# HIVE_BOARD_DEBUG.net
KiCad netlist of a schematic drawn in Altium Designer
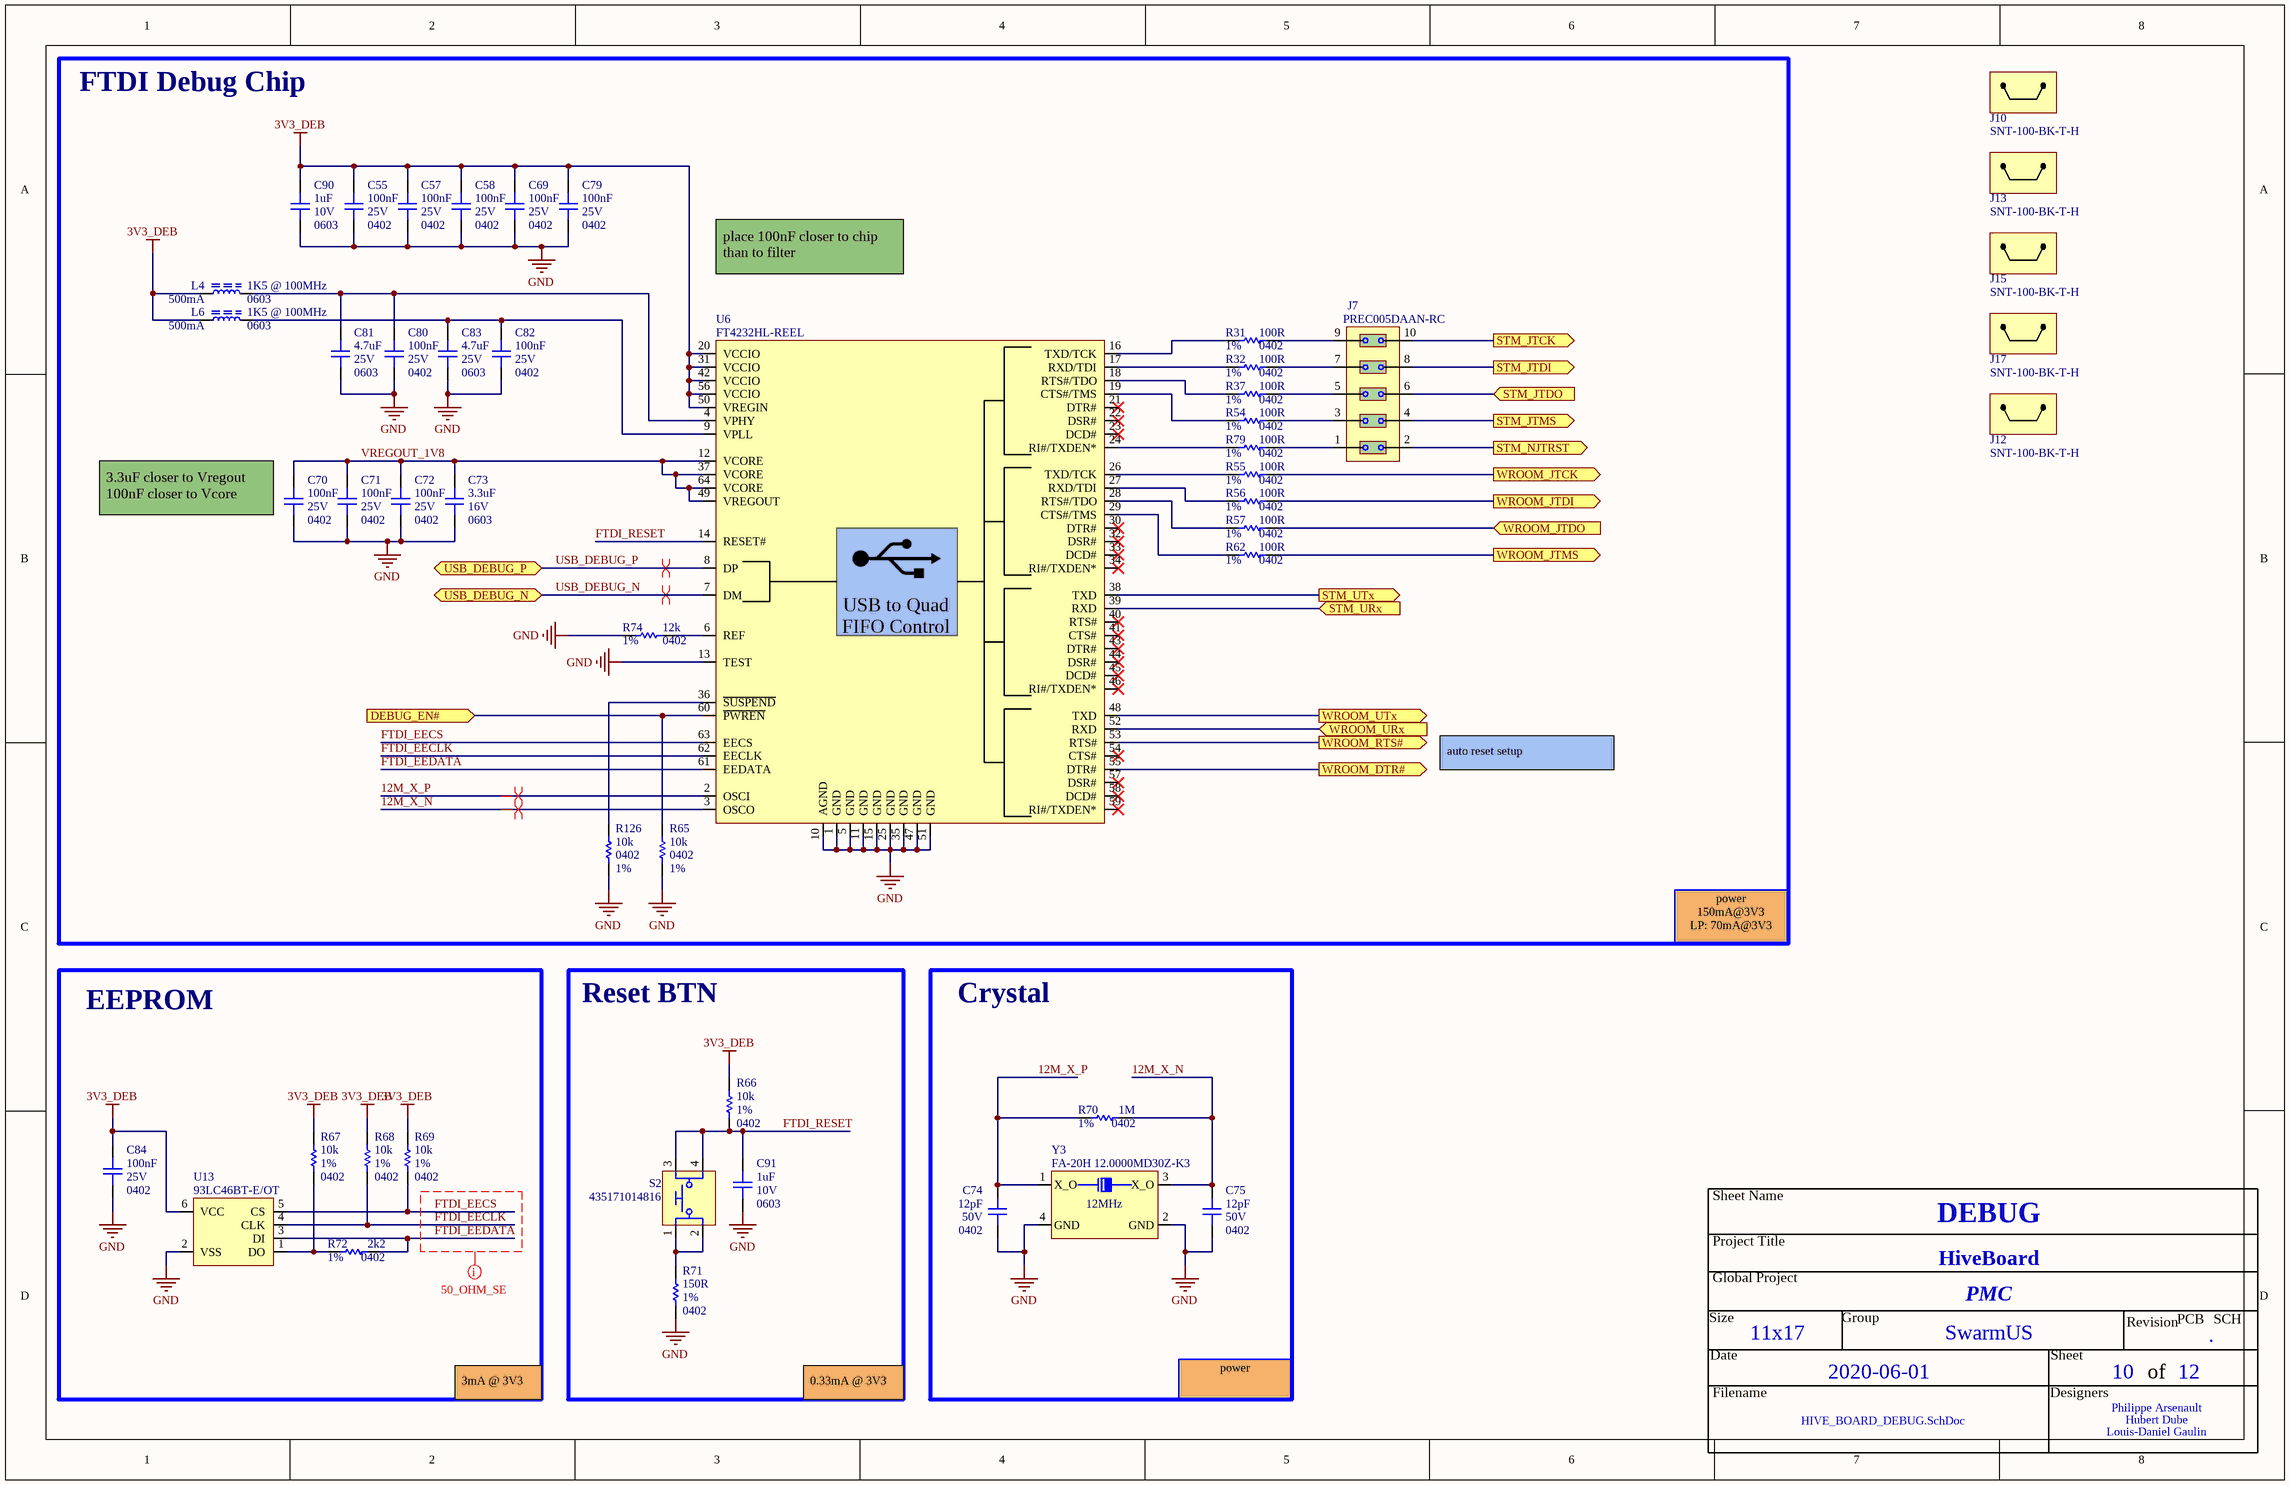
[diagram p0: HIVE_BOARD_DEBUG.SchDoc]

(export (version "E")
  (design (tool "Eeschema 10.0.6"))
  (components
    (comp (ref "C55")
      (value "100nF")
      (footprint "CAP_CER_0402")
      (description "CAP - CER 0.1µF 10% 25V X7R - 0402")
      (fields
        (field (name "TOLERANCE") "10%")
        (field (name "PACKAGE") "0402")
        (field (name "VOLTAGE RATING") "25V")
        (field (name "Comment") "CGA2B3X7R1E104K050BB")
        (field (name "CREATEDBY/DATE") "Nicolas Roy 2018-11-07")
        (field (name "VERIFIEDBY") "Nicolas V. (2019-01-22)")
      )
      (libsource (lib "GRAMS_MASTER_LIB") (part "CAP_CER_CGA2B3X7R1E104K050BB"))
    )
    (comp (ref "C57")
      (value "100nF")
      (footprint "CAP_CER_0402")
      (description "CAP - CER 0.1µF 10% 25V X7R - 0402")
      (fields
        (field (name "TOLERANCE") "10%")
        (field (name "PACKAGE") "0402")
        (field (name "VOLTAGE RATING") "25V")
        (field (name "Comment") "CGA2B3X7R1E104K050BB")
        (field (name "CREATEDBY/DATE") "Nicolas Roy 2018-11-07")
        (field (name "VERIFIEDBY") "Nicolas V. (2019-01-22)")
      )
      (libsource (lib "GRAMS_MASTER_LIB") (part "CAP_CER_CGA2B3X7R1E104K050BB"))
    )
    (comp (ref "C58")
      (value "100nF")
      (footprint "CAP_CER_0402")
      (description "CAP - CER 0.1µF 10% 25V X7R - 0402")
      (fields
        (field (name "TOLERANCE") "10%")
        (field (name "PACKAGE") "0402")
        (field (name "VOLTAGE RATING") "25V")
        (field (name "Comment") "CGA2B3X7R1E104K050BB")
        (field (name "CREATEDBY/DATE") "Nicolas Roy 2018-11-07")
        (field (name "VERIFIEDBY") "Nicolas V. (2019-01-22)")
      )
      (libsource (lib "GRAMS_MASTER_LIB") (part "CAP_CER_CGA2B3X7R1E104K050BB"))
    )
    (comp (ref "C69")
      (value "100nF")
      (footprint "CAP_CER_0402")
      (description "CAP - CER 0.1µF 10% 25V X7R - 0402")
      (fields
        (field (name "TOLERANCE") "10%")
        (field (name "PACKAGE") "0402")
        (field (name "VOLTAGE RATING") "25V")
        (field (name "Comment") "CGA2B3X7R1E104K050BB")
        (field (name "CREATEDBY/DATE") "Nicolas Roy 2018-11-07")
        (field (name "VERIFIEDBY") "Nicolas V. (2019-01-22)")
      )
      (libsource (lib "GRAMS_MASTER_LIB") (part "CAP_CER_CGA2B3X7R1E104K050BB"))
    )
    (comp (ref "C70")
      (value "100nF")
      (footprint "CAP_CER_0402")
      (description "CAP - CER 0.1µF 10% 25V X7R - 0402")
      (fields
        (field (name "TOLERANCE") "10%")
        (field (name "PACKAGE") "0402")
        (field (name "VOLTAGE RATING") "25V")
        (field (name "Comment") "CGA2B3X7R1E104K050BB")
        (field (name "CREATEDBY/DATE") "Nicolas Roy 2018-11-07")
        (field (name "VERIFIEDBY") "Nicolas V. (2019-01-22)")
      )
      (libsource (lib "GRAMS_MASTER_LIB") (part "CAP_CER_CGA2B3X7R1E104K050BB"))
    )
    (comp (ref "C71")
      (value "100nF")
      (footprint "CAP_CER_0402")
      (description "CAP - CER 0.1µF 10% 25V X7R - 0402")
      (fields
        (field (name "TOLERANCE") "10%")
        (field (name "PACKAGE") "0402")
        (field (name "VOLTAGE RATING") "25V")
        (field (name "Comment") "CGA2B3X7R1E104K050BB")
        (field (name "CREATEDBY/DATE") "Nicolas Roy 2018-11-07")
        (field (name "VERIFIEDBY") "Nicolas V. (2019-01-22)")
      )
      (libsource (lib "GRAMS_MASTER_LIB") (part "CAP_CER_CGA2B3X7R1E104K050BB"))
    )
    (comp (ref "C72")
      (value "100nF")
      (footprint "CAP_CER_0402")
      (description "CAP - CER 0.1µF 10% 25V X7R - 0402")
      (fields
        (field (name "TOLERANCE") "10%")
        (field (name "PACKAGE") "0402")
        (field (name "VOLTAGE RATING") "25V")
        (field (name "Comment") "CGA2B3X7R1E104K050BB")
        (field (name "CREATEDBY/DATE") "Nicolas Roy 2018-11-07")
        (field (name "VERIFIEDBY") "Nicolas V. (2019-01-22)")
      )
      (libsource (lib "GRAMS_MASTER_LIB") (part "CAP_CER_CGA2B3X7R1E104K050BB"))
    )
    (comp (ref "C73")
      (value "3.3uF")
      (footprint "CAP_CER_0603")
      (description "CAP - CER 3.3µF ±10% 16V Ceramic Capacitor X5R 0603 (1608 Metric)")
      (fields
        (field (name "TOLERANCE") "10%")
        (field (name "PACKAGE") "0603")
        (field (name "VOLTAGE RATING") "16V")
        (field (name "Comment") "C1608X5R1C335K080AC")
        (field (name "CREATEDBY/DATE") "Hubert Dube - 16/03/2021")
        (field (name "VERIFIEDBY") "Philippe Arsenault - 2021/03/16")
      )
      (libsource (lib "SWARMUS_LIB") (part "CAP_CER_C1608X5R1C335K080AC"))
    )
    (comp (ref "C74")
      (value "12pF")
      (footprint "CAP_CER_0402")
      (description "CAP - CER 12pF 50V ±5% C0G, NP0 - 0402")
      (fields
        (field (name "TOLERANCE") "±5%")
        (field (name "PACKAGE") "0402")
        (field (name "VOLTAGE RATING") "50V")
        (field (name "Comment") "CC0402JRNPO9BN120")
        (field (name "CREATEDBY/DATE") "Philippe Arsenault/ 2020-07-24")
        (field (name "VERIFIEDBY") "Louis-Daniel Gaulin / 2020-07-29")
      )
      (libsource (lib "SWARMUS_LIB") (part "CAP_CER_CC0402JRNPO9BN120"))
    )
    (comp (ref "C75")
      (value "12pF")
      (footprint "CAP_CER_0402")
      (description "CAP - CER 12pF 50V ±5% C0G, NP0 - 0402")
      (fields
        (field (name "TOLERANCE") "±5%")
        (field (name "PACKAGE") "0402")
        (field (name "VOLTAGE RATING") "50V")
        (field (name "Comment") "CC0402JRNPO9BN120")
        (field (name "CREATEDBY/DATE") "Philippe Arsenault/ 2020-07-24")
        (field (name "VERIFIEDBY") "Louis-Daniel Gaulin / 2020-07-29")
      )
      (libsource (lib "SWARMUS_LIB") (part "CAP_CER_CC0402JRNPO9BN120"))
    )
    (comp (ref "C79")
      (value "100nF")
      (footprint "CAP_CER_0402")
      (description "CAP - CER 0.1µF 10% 25V X7R - 0402")
      (fields
        (field (name "TOLERANCE") "10%")
        (field (name "PACKAGE") "0402")
        (field (name "VOLTAGE RATING") "25V")
        (field (name "Comment") "CGA2B3X7R1E104K050BB")
        (field (name "CREATEDBY/DATE") "Nicolas Roy 2018-11-07")
        (field (name "VERIFIEDBY") "Nicolas V. (2019-01-22)")
      )
      (libsource (lib "GRAMS_MASTER_LIB") (part "CAP_CER_CGA2B3X7R1E104K050BB"))
    )
    (comp (ref "C80")
      (value "100nF")
      (footprint "CAP_CER_0402")
      (description "CAP - CER 0.1µF 10% 25V X7R - 0402")
      (fields
        (field (name "TOLERANCE") "10%")
        (field (name "PACKAGE") "0402")
        (field (name "VOLTAGE RATING") "25V")
        (field (name "Comment") "CGA2B3X7R1E104K050BB")
        (field (name "CREATEDBY/DATE") "Nicolas Roy 2018-11-07")
        (field (name "VERIFIEDBY") "Nicolas V. (2019-01-22)")
      )
      (libsource (lib "GRAMS_MASTER_LIB") (part "CAP_CER_CGA2B3X7R1E104K050BB"))
    )
    (comp (ref "C81")
      (value "4.7uF")
      (footprint "CAP_CER_0603")
      (description "CAP - CER 4.7µF 20% 25V X5R - 0603")
      (fields
        (field (name "TOLERANCE") "20%")
        (field (name "PACKAGE") "0603")
        (field (name "VOLTAGE RATING") "25V")
        (field (name "Comment") "CL10A475MA8NQNC")
        (field (name "CREATEDBY/DATE") "Nicolas Roy 2018-11-21")
        (field (name "VERIFIEDBY") "Nicolas V. (2019-01-22)")
      )
      (libsource (lib "GRAMS_MASTER_LIB") (part "CAP_CER_CL10A475MA8NQNC"))
    )
    (comp (ref "C82")
      (value "100nF")
      (footprint "CAP_CER_0402")
      (description "CAP - CER 0.1µF 10% 25V X7R - 0402")
      (fields
        (field (name "TOLERANCE") "10%")
        (field (name "PACKAGE") "0402")
        (field (name "VOLTAGE RATING") "25V")
        (field (name "Comment") "CGA2B3X7R1E104K050BB")
        (field (name "CREATEDBY/DATE") "Nicolas Roy 2018-11-07")
        (field (name "VERIFIEDBY") "Nicolas V. (2019-01-22)")
      )
      (libsource (lib "GRAMS_MASTER_LIB") (part "CAP_CER_CGA2B3X7R1E104K050BB"))
    )
    (comp (ref "C83")
      (value "4.7uF")
      (footprint "CAP_CER_0603")
      (description "CAP - CER 4.7µF 20% 25V X5R - 0603")
      (fields
        (field (name "TOLERANCE") "20%")
        (field (name "PACKAGE") "0603")
        (field (name "VOLTAGE RATING") "25V")
        (field (name "Comment") "CL10A475MA8NQNC")
        (field (name "CREATEDBY/DATE") "Nicolas Roy 2018-11-21")
        (field (name "VERIFIEDBY") "Nicolas V. (2019-01-22)")
      )
      (libsource (lib "GRAMS_MASTER_LIB") (part "CAP_CER_CL10A475MA8NQNC"))
    )
    (comp (ref "C84")
      (value "100nF")
      (footprint "CAP_CER_0402")
      (description "CAP - CER 0.1µF 10% 25V X7R - 0402")
      (fields
        (field (name "TOLERANCE") "10%")
        (field (name "PACKAGE") "0402")
        (field (name "VOLTAGE RATING") "25V")
        (field (name "Comment") "CGA2B3X7R1E104K050BB")
        (field (name "CREATEDBY/DATE") "Nicolas Roy 2018-11-07")
        (field (name "VERIFIEDBY") "Nicolas V. (2019-01-22)")
      )
      (libsource (lib "GRAMS_MASTER_LIB") (part "CAP_CER_CGA2B3X7R1E104K050BB"))
    )
    (comp (ref "C90")
      (value "1uF")
      (footprint "CAP_CER_0603")
      (description "CAP - CER 1uF 10V 10% X5R - 0603")
      (fields
        (field (name "TOLERANCE") "10%")
        (field (name "PACKAGE") "0603")
        (field (name "VOLTAGE RATING") "10V")
        (field (name "Comment") "C0603C105K8PACTU")
        (field (name "CREATEDBY/DATE") "Hubert Dube - 21/07/20")
        (field (name "VERIFIEDBY") "Louis-Daniel Gaulin - 21/07/20")
      )
      (libsource (lib "SWARMUS_LIB") (part "CAP_CER_C0603C105K8PACTU"))
    )
    (comp (ref "C91")
      (value "1uF")
      (footprint "CAP_CER_0603")
      (description "CAP - CER 1uF 10V 10% X5R - 0603")
      (fields
        (field (name "TOLERANCE") "10%")
        (field (name "PACKAGE") "0603")
        (field (name "VOLTAGE RATING") "10V")
        (field (name "Comment") "C0603C105K8PACTU")
        (field (name "CREATEDBY/DATE") "Hubert Dube - 21/07/20")
        (field (name "VERIFIEDBY") "Louis-Daniel Gaulin - 21/07/20")
      )
      (libsource (lib "SWARMUS_LIB") (part "CAP_CER_C0603C105K8PACTU"))
    )
    (comp (ref "J7")
      (value "PREC005DAAN-RC")
      (footprint "CON_HDR_PREC009DAAN-RC")
      (description "CON - Connector Header Through Hole 10 position 0.100\" (2.54mm)")
      (fields
        (field (name "VERIFIEDBY") "Louis-Daniel Gaulin / 08-04-2021")
        (field (name "CREATEDBY/DATE") "Philippe Arsenault/2021-03-27")
      )
      (libsource (lib "SWARMUS_LIB") (part "CON_HDR_PREC005DAAN-RC"))
    )
    (comp (ref "J10")
      (value "SNT-100-BK-T-H")
      (footprint "CON_JMP_SNT-100-BK-T-H")
      (description "CON - CONN SHUNT - MEC")
      (fields
        (field (name "CREATEDBY/DATE") "Arnaud Samson - 09/07/18")
        (field (name "VERIFIEDBY") "Jonathan Bouchard 2018-07-12")
      )
      (libsource (lib "GRAMS_MASTER_LIB") (part "CON_JMP_SNT-100-BK-T-H"))
    )
    (comp (ref "J12")
      (value "SNT-100-BK-T-H")
      (footprint "CON_JMP_SNT-100-BK-T-H")
      (description "CON - CONN SHUNT - MEC")
      (fields
        (field (name "CREATEDBY/DATE") "Arnaud Samson - 09/07/18")
        (field (name "VERIFIEDBY") "Jonathan Bouchard 2018-07-12")
      )
      (libsource (lib "GRAMS_MASTER_LIB") (part "CON_JMP_SNT-100-BK-T-H"))
    )
    (comp (ref "J13")
      (value "SNT-100-BK-T-H")
      (footprint "CON_JMP_SNT-100-BK-T-H")
      (description "CON - CONN SHUNT - MEC")
      (fields
        (field (name "CREATEDBY/DATE") "Arnaud Samson - 09/07/18")
        (field (name "VERIFIEDBY") "Jonathan Bouchard 2018-07-12")
      )
      (libsource (lib "GRAMS_MASTER_LIB") (part "CON_JMP_SNT-100-BK-T-H"))
    )
    (comp (ref "J15")
      (value "SNT-100-BK-T-H")
      (footprint "CON_JMP_SNT-100-BK-T-H")
      (description "CON - CONN SHUNT - MEC")
      (fields
        (field (name "CREATEDBY/DATE") "Arnaud Samson - 09/07/18")
        (field (name "VERIFIEDBY") "Jonathan Bouchard 2018-07-12")
      )
      (libsource (lib "GRAMS_MASTER_LIB") (part "CON_JMP_SNT-100-BK-T-H"))
    )
    (comp (ref "J17")
      (value "SNT-100-BK-T-H")
      (footprint "CON_JMP_SNT-100-BK-T-H")
      (description "CON - CONN SHUNT - MEC")
      (fields
        (field (name "CREATEDBY/DATE") "Arnaud Samson - 09/07/18")
        (field (name "VERIFIEDBY") "Jonathan Bouchard 2018-07-12")
      )
      (libsource (lib "GRAMS_MASTER_LIB") (part "CON_JMP_SNT-100-BK-T-H"))
    )
    (comp (ref "L4")
      (value "1K5 @ 100MHz")
      (footprint "FER_0603")
      (description "FER - 1.5 kOhms @ 100MHz 1 Signal Line Ferrite Bead 0603 (1608 Metric) 500mA 500mOhm DC")
      (fields
        (field (name "CURRENT RATING") "500mA")
        (field (name "PACKAGE") "0603")
        (field (name "Comment") "BLM18HE152SN1D")
        (field (name "CREATEDBY/DATE") "Hubert Dube - 16/03/2021")
        (field (name "VERIFIEDBY") "Philippe Arsenault - 2021-03-16")
      )
      (libsource (lib "SWARMUS_LIB") (part "FER_BLM18HE152SN1D"))
    )
    (comp (ref "L6")
      (value "1K5 @ 100MHz")
      (footprint "FER_0603")
      (description "FER - 1.5 kOhms @ 100MHz 1 Signal Line Ferrite Bead 0603 (1608 Metric) 500mA 500mOhm DC")
      (fields
        (field (name "CURRENT RATING") "500mA")
        (field (name "PACKAGE") "0603")
        (field (name "Comment") "BLM18HE152SN1D")
        (field (name "CREATEDBY/DATE") "Hubert Dube - 16/03/2021")
        (field (name "VERIFIEDBY") "Philippe Arsenault - 2021-03-16")
      )
      (libsource (lib "SWARMUS_LIB") (part "FER_BLM18HE152SN1D"))
    )
    (comp (ref "R31")
      (value "100R")
      (footprint "RES_0402")
      (description "RES - 100R OHM 1% 1/16W - 0402")
      (fields
        (field (name "TOLERANCE") "1%")
        (field (name "PACKAGE") "0402")
        (field (name "Comment") "RC0402FR-07100RP")
        (field (name "CREATEDBY/DATE") "Jonathan Bouchard 2018-07-05")
        (field (name "VERIFIEDBY") "Arnaud Samson 16-07-18")
      )
      (libsource (lib "GRAMS_MASTER_LIB") (part "RES_RC0402FR-07100RP"))
    )
    (comp (ref "R32")
      (value "100R")
      (footprint "RES_0402")
      (description "RES - 100R OHM 1% 1/16W - 0402")
      (fields
        (field (name "TOLERANCE") "1%")
        (field (name "PACKAGE") "0402")
        (field (name "Comment") "RC0402FR-07100RP")
        (field (name "CREATEDBY/DATE") "Jonathan Bouchard 2018-07-05")
        (field (name "VERIFIEDBY") "Arnaud Samson 16-07-18")
      )
      (libsource (lib "GRAMS_MASTER_LIB") (part "RES_RC0402FR-07100RP"))
    )
    (comp (ref "R37")
      (value "100R")
      (footprint "RES_0402")
      (description "RES - 100R OHM 1% 1/16W - 0402")
      (fields
        (field (name "TOLERANCE") "1%")
        (field (name "PACKAGE") "0402")
        (field (name "Comment") "RC0402FR-07100RP")
        (field (name "CREATEDBY/DATE") "Jonathan Bouchard 2018-07-05")
        (field (name "VERIFIEDBY") "Arnaud Samson 16-07-18")
      )
      (libsource (lib "GRAMS_MASTER_LIB") (part "RES_RC0402FR-07100RP"))
    )
    (comp (ref "R54")
      (value "100R")
      (footprint "RES_0402")
      (description "RES - 100R OHM 1% 1/16W - 0402")
      (fields
        (field (name "TOLERANCE") "1%")
        (field (name "PACKAGE") "0402")
        (field (name "Comment") "RC0402FR-07100RP")
        (field (name "CREATEDBY/DATE") "Jonathan Bouchard 2018-07-05")
        (field (name "VERIFIEDBY") "Arnaud Samson 16-07-18")
      )
      (libsource (lib "GRAMS_MASTER_LIB") (part "RES_RC0402FR-07100RP"))
    )
    (comp (ref "R55")
      (value "100R")
      (footprint "RES_0402")
      (description "RES - 100R OHM 1% 1/16W - 0402")
      (fields
        (field (name "TOLERANCE") "1%")
        (field (name "PACKAGE") "0402")
        (field (name "Comment") "RC0402FR-07100RP")
        (field (name "CREATEDBY/DATE") "Jonathan Bouchard 2018-07-05")
        (field (name "VERIFIEDBY") "Arnaud Samson 16-07-18")
      )
      (libsource (lib "GRAMS_MASTER_LIB") (part "RES_RC0402FR-07100RP"))
    )
    (comp (ref "R56")
      (value "100R")
      (footprint "RES_0402")
      (description "RES - 100R OHM 1% 1/16W - 0402")
      (fields
        (field (name "TOLERANCE") "1%")
        (field (name "PACKAGE") "0402")
        (field (name "Comment") "RC0402FR-07100RP")
        (field (name "CREATEDBY/DATE") "Jonathan Bouchard 2018-07-05")
        (field (name "VERIFIEDBY") "Arnaud Samson 16-07-18")
      )
      (libsource (lib "GRAMS_MASTER_LIB") (part "RES_RC0402FR-07100RP"))
    )
    (comp (ref "R57")
      (value "100R")
      (footprint "RES_0402")
      (description "RES - 100R OHM 1% 1/16W - 0402")
      (fields
        (field (name "TOLERANCE") "1%")
        (field (name "PACKAGE") "0402")
        (field (name "Comment") "RC0402FR-07100RP")
        (field (name "CREATEDBY/DATE") "Jonathan Bouchard 2018-07-05")
        (field (name "VERIFIEDBY") "Arnaud Samson 16-07-18")
      )
      (libsource (lib "GRAMS_MASTER_LIB") (part "RES_RC0402FR-07100RP"))
    )
    (comp (ref "R62")
      (value "100R")
      (footprint "RES_0402")
      (description "RES - 100R OHM 1% 1/16W - 0402")
      (fields
        (field (name "TOLERANCE") "1%")
        (field (name "PACKAGE") "0402")
        (field (name "Comment") "RC0402FR-07100RP")
        (field (name "CREATEDBY/DATE") "Jonathan Bouchard 2018-07-05")
        (field (name "VERIFIEDBY") "Arnaud Samson 16-07-18")
      )
      (libsource (lib "GRAMS_MASTER_LIB") (part "RES_RC0402FR-07100RP"))
    )
    (comp (ref "R65")
      (value "10k")
      (footprint "RES_0402")
      (description "RES - 10K OHMS 1% 1/16W - 0402")
      (fields
        (field (name "TOLERANCE") "1%")
        (field (name "PACKAGE") "0402")
        (field (name "Comment") "RC0402FR-0710KL")
        (field (name "CREATEDBY/DATE") "Nicolas V. (2018-11-20)")
        (field (name "VERIFIEDBY") "Nicolas V. (2018-11-20)")
      )
      (libsource (lib "GRAMS_MASTER_LIB") (part "RES_RC0402FR-0710KL"))
    )
    (comp (ref "R66")
      (value "10k")
      (footprint "RES_0402")
      (description "RES - 10K OHMS 1% 1/16W - 0402")
      (fields
        (field (name "TOLERANCE") "1%")
        (field (name "PACKAGE") "0402")
        (field (name "Comment") "RC0402FR-0710KL")
        (field (name "CREATEDBY/DATE") "Nicolas V. (2018-11-20)")
        (field (name "VERIFIEDBY") "Nicolas V. (2018-11-20)")
      )
      (libsource (lib "GRAMS_MASTER_LIB") (part "RES_RC0402FR-0710KL"))
    )
    (comp (ref "R67")
      (value "10k")
      (footprint "RES_0402")
      (description "RES - 10K OHMS 1% 1/16W - 0402")
      (fields
        (field (name "TOLERANCE") "1%")
        (field (name "PACKAGE") "0402")
        (field (name "Comment") "RC0402FR-0710KL")
        (field (name "CREATEDBY/DATE") "Nicolas V. (2018-11-20)")
        (field (name "VERIFIEDBY") "Nicolas V. (2018-11-20)")
      )
      (libsource (lib "GRAMS_MASTER_LIB") (part "RES_RC0402FR-0710KL"))
    )
    (comp (ref "R68")
      (value "10k")
      (footprint "RES_0402")
      (description "RES - 10K OHMS 1% 1/16W - 0402")
      (fields
        (field (name "TOLERANCE") "1%")
        (field (name "PACKAGE") "0402")
        (field (name "Comment") "RC0402FR-0710KL")
        (field (name "CREATEDBY/DATE") "Nicolas V. (2018-11-20)")
        (field (name "VERIFIEDBY") "Nicolas V. (2018-11-20)")
      )
      (libsource (lib "GRAMS_MASTER_LIB") (part "RES_RC0402FR-0710KL"))
    )
    (comp (ref "R69")
      (value "10k")
      (footprint "RES_0402")
      (description "RES - 10K OHMS 1% 1/16W - 0402")
      (fields
        (field (name "TOLERANCE") "1%")
        (field (name "PACKAGE") "0402")
        (field (name "Comment") "RC0402FR-0710KL")
        (field (name "CREATEDBY/DATE") "Nicolas V. (2018-11-20)")
        (field (name "VERIFIEDBY") "Nicolas V. (2018-11-20)")
      )
      (libsource (lib "GRAMS_MASTER_LIB") (part "RES_RC0402FR-0710KL"))
    )
    (comp (ref "R70")
      (value "1M")
      (footprint "RES_0402")
      (description "RES - 1 MOhms ±1% 0.063W, 1/16W Chip Resistor 0402 (1005 Metric) Moisture Resistant Thick Film")
      (fields
        (field (name "TOLERANCE") "1%")
        (field (name "PACKAGE") "0402")
        (field (name "Comment") "RC0402FR-071ML")
        (field (name "CREATEDBY/DATE") "Hubert Dube 16/03/2021")
        (field (name "VERIFIEDBY") "Philippe Arsenault - 2021/03/16")
      )
      (libsource (lib "SWARMUS_LIB") (part "RES_RC0402FR-071ML"))
    )
    (comp (ref "R71")
      (value "150R")
      (footprint "RES_0402")
      (description "RES - 150R 1% 1/16W - 0402")
      (fields
        (field (name "TOLERANCE") "1%")
        (field (name "PACKAGE") "0402")
        (field (name "Comment") "RC0402FR-07150RL")
        (field (name "CREATEDBY/DATE") "Jonathan Bouchard 2019-03-25")
        (field (name "VERIFIEDBY") "Nicolas V. (2019-05-02)")
      )
      (libsource (lib "GRAMS_MASTER_LIB") (part "RES_RC0402FR-07150RL"))
    )
    (comp (ref "R72")
      (value "2k2")
      (footprint "RES_0402")
      (description "RES - 2.2K 1% 1/16W - 0402")
      (fields
        (field (name "TOLERANCE") "1%")
        (field (name "PACKAGE") "0402")
        (field (name "Comment") "RC0402FR-072K2L")
        (field (name "CREATEDBY/DATE") "Keven Deslandes 2018-11-14")
        (field (name "VERIFIEDBY") "Caroline Paulin - 8 janv 2019")
      )
      (libsource (lib "GRAMS_MASTER_LIB") (part "RES_RC0402FR-072K2L"))
    )
    (comp (ref "R74")
      (value "12k")
      (footprint "RES_0402")
      (description "RES - 12k Ohms ±1% 0.063W, 1/16W Chip Resistor 0402 (1005 Metric) Moisture Resistant Thick Film")
      (fields
        (field (name "TOLERANCE") "1%")
        (field (name "PACKAGE") "0402")
        (field (name "Comment") "RC0402FR-0712KL")
        (field (name "CREATEDBY/DATE") "Philippe Arsenault/2021-03-11")
        (field (name "VERIFIEDBY") "Hubert Dube - 19/03/2021")
      )
      (libsource (lib "SWARMUS_LIB") (part "RES_RC0402FR-0712KL"))
    )
    (comp (ref "R79")
      (value "100R")
      (footprint "RES_0402")
      (description "RES - 100R OHM 1% 1/16W - 0402")
      (fields
        (field (name "TOLERANCE") "1%")
        (field (name "PACKAGE") "0402")
        (field (name "Comment") "RC0402FR-07100RP")
        (field (name "CREATEDBY/DATE") "Jonathan Bouchard 2018-07-05")
        (field (name "VERIFIEDBY") "Arnaud Samson 16-07-18")
      )
      (libsource (lib "GRAMS_MASTER_LIB") (part "RES_RC0402FR-07100RP"))
    )
    (comp (ref "R126")
      (value "10k")
      (footprint "RES_0402")
      (description "RES - 10K OHMS 1% 1/16W - 0402")
      (fields
        (field (name "TOLERANCE") "1%")
        (field (name "PACKAGE") "0402")
        (field (name "Comment") "RC0402FR-0710KL")
        (field (name "CREATEDBY/DATE") "Nicolas V. (2018-11-20)")
        (field (name "VERIFIEDBY") "Nicolas V. (2018-11-20)")
      )
      (libsource (lib "GRAMS_MASTER_LIB") (part "RES_RC0402FR-0710KL"))
    )
    (comp (ref "S2")
      (value "435171014816")
      (footprint "SWI_TACT_435171014816")
      (description "SWI - SWITCH TACTILE SPST-NO 0.05A 12V -SMD")
      (fields
        (field (name "CREATEDBY/DATE") "Hubert Dube - 22/07/20")
        (field (name "VERIFIEDBY") "Louis-Daniel Gaulin / 12-11-2020")
      )
      (libsource (lib "SWARMUS_LIB") (part "SWI_TACT_435171014816"))
    )
    (comp (ref "U6")
      (value "FT4232HL-REEL")
      (footprint "COM_USB_FT4232HL-REEL")
      (description "COM_USB - Bridge, USB to UART,FIFO USB 2.0 FIFO, JTAG Quad channel Interface -  64-LQFP (10x10)")
      (fields
        (field (name "VERIFIEDBY") "Louis-Daniel Gaulin / 08-04-2021")
        (field (name "CREATEDBY/DATE") "Philippe Arsenault/2021-04-07")
      )
      (libsource (lib "SWARMUS_LIB") (part "COM_USB_FT4232HL-REEL"))
    )
    (comp (ref "U13")
      (value "93LC46BT-E/OT")
      (footprint "MEM_EEPROM_93LC46BT-E/OT")
      (description "EEPROM Memory IC 1Kb (128 x 8) SPI 2MHz  SOT-23-6")
      (fields
        (field (name "VERIFIEDBY") "Philippe Arsenault - 17/03/2021 + HD 19/03/2021")
        (field (name "CREATEDBY/DATE") "Hubert Dube -  13/03/2021")
      )
      (libsource (lib "SWARMUS_LIB") (part "MEM_EEPROM_93LC46BT-E/OT"))
    )
    (comp (ref "Y3")
      (value "FA-20H 12.0000MD30Z-K3")
      (footprint "CRY_FA-20H")
      (description "CRY - 12MHz ±30ppm Crystal 10pF 150 Ohms 4-SMD, No Lead")
      (fields
        (field (name "TOLERANCE") "±30ppm")
        (field (name "CREATEDBY/DATE") "Hubert Dube - 13/03/2021")
        (field (name "VERIFIEDBY") "Philippe Arsenault - 2021/03/16")
      )
      (libsource (lib "SWARMUS_LIB") (part "CRY_FA-20H 12.0000MD30Z-K3"))
    )
  )
  (nets
    (net (code "1") (name "/12M_X_N") (class "Default")
      (node (ref "C75") (pin "2") (pinfunction "2_2") (pintype "passive"))
      (node (ref "R70") (pin "1") (pinfunction "1_1") (pintype "passive"))
      (node (ref "U6") (pin "3") (pinfunction "OSCO_3") (pintype "passive"))
      (node (ref "Y3") (pin "3") (pinfunction "X_O_3") (pintype "passive"))
    )
    (net (code "2") (name "/12M_X_P") (class "Default")
      (node (ref "C74") (pin "2") (pinfunction "2_2") (pintype "passive"))
      (node (ref "R70") (pin "2") (pinfunction "2_2") (pintype "passive"))
      (node (ref "U6") (pin "2") (pinfunction "OSCI_2") (pintype "passive"))
      (node (ref "Y3") (pin "1") (pinfunction "X_O_1") (pintype "passive"))
    )
    (net (code "3") (name "/DEBUG_EN#") (class "Default")
      (node (ref "R65") (pin "1") (pinfunction "1_1") (pintype "passive"))
      (node (ref "U6") (pin "60") (pinfunction "PWREN_60") (pintype "passive"))
    )
    (net (code "4") (name "/FTDI_EECLK") (class "Default")
      (node (ref "R68") (pin "1") (pinfunction "1_1") (pintype "passive"))
      (node (ref "U13") (pin "4") (pinfunction "CLK_4") (pintype "passive"))
      (node (ref "U6") (pin "62") (pinfunction "EECLK_62") (pintype "passive"))
    )
    (net (code "5") (name "/FTDI_EECS") (class "Default")
      (node (ref "R69") (pin "1") (pinfunction "1_1") (pintype "passive"))
      (node (ref "U13") (pin "5") (pinfunction "CS_5") (pintype "passive"))
      (node (ref "U6") (pin "63") (pinfunction "EECS_63") (pintype "passive"))
    )
    (net (code "6") (name "/FTDI_EEDATA") (class "Default")
      (node (ref "R72") (pin "1") (pinfunction "1_1") (pintype "passive"))
      (node (ref "U13") (pin "3") (pinfunction "DI_3") (pintype "passive"))
      (node (ref "U6") (pin "61") (pinfunction "EEDATA_61") (pintype "passive"))
    )
    (net (code "7") (name "/FTDI_RESET") (class "Default")
      (node (ref "C91") (pin "1") (pinfunction "1_1") (pintype "passive"))
      (node (ref "R66") (pin "1") (pinfunction "1_1") (pintype "passive"))
      (node (ref "S2") (pin "3") (pinfunction "3_3") (pintype "passive"))
      (node (ref "S2") (pin "4") (pinfunction "4_4") (pintype "passive"))
      (node (ref "U6") (pin "14") (pinfunction "RESET#_14") (pintype "passive"))
    )
    (net (code "8") (name "/STM_JTCK") (class "Default") (node (ref "J7") (pin "10") (pintype "passive")))
    (net (code "9") (name "/STM_JTDI") (class "Default") (node (ref "J7") (pin "8") (pintype "passive")))
    (net (code "10") (name "/STM_JTDO") (class "Default") (node (ref "J7") (pin "6") (pintype "passive")))
    (net (code "11") (name "/STM_JTMS") (class "Default") (node (ref "J7") (pin "4") (pintype "passive")))
    (net (code "12") (name "/STM_NJTRST") (class "Default") (node (ref "J7") (pin "2") (pintype "passive")))
    (net (code "13") (name "/STM_URx") (class "Default")
      (node (ref "U6") (pin "39") (pinfunction "RXD_39") (pintype "passive"))
    )
    (net (code "14") (name "/STM_UTx") (class "Default")
      (node (ref "U6") (pin "38") (pinfunction "TXD_38") (pintype "passive"))
    )
    (net (code "15") (name "/USB_DEBUG_N") (class "Default")
      (node (ref "U6") (pin "7") (pinfunction "DM_7") (pintype "passive"))
    )
    (net (code "16") (name "/USB_DEBUG_P") (class "Default")
      (node (ref "U6") (pin "8") (pinfunction "DP_8") (pintype "passive"))
    )
    (net (code "17") (name "/VREGOUT_1V8") (class "Default")
      (node (ref "C70") (pin "1") (pinfunction "1_1") (pintype "passive"))
      (node (ref "C71") (pin "1") (pinfunction "1_1") (pintype "passive"))
      (node (ref "C72") (pin "1") (pinfunction "1_1") (pintype "passive"))
      (node (ref "C73") (pin "2") (pinfunction "2_2") (pintype "passive"))
      (node (ref "U6") (pin "12") (pinfunction "VCORE_12") (pintype "passive"))
      (node (ref "U6") (pin "37") (pinfunction "VCORE_37") (pintype "passive"))
      (node (ref "U6") (pin "49") (pinfunction "VREGOUT_49") (pintype "passive"))
      (node (ref "U6") (pin "64") (pinfunction "VCORE_64") (pintype "passive"))
    )
    (net (code "18") (name "/WROOM_DTR#") (class "Default")
      (node (ref "U6") (pin "55") (pinfunction "DTR#_55") (pintype "passive"))
    )
    (net (code "19") (name "/WROOM_JTCK") (class "Default")
      (node (ref "R55") (pin "1") (pinfunction "1_1") (pintype "passive"))
    )
    (net (code "20") (name "/WROOM_JTDI") (class "Default")
      (node (ref "R56") (pin "1") (pinfunction "1_1") (pintype "passive"))
    )
    (net (code "21") (name "/WROOM_JTDO") (class "Default")
      (node (ref "R57") (pin "1") (pinfunction "1_1") (pintype "passive"))
    )
    (net (code "22") (name "/WROOM_JTMS") (class "Default")
      (node (ref "R62") (pin "1") (pinfunction "1_1") (pintype "passive"))
    )
    (net (code "23") (name "/WROOM_RTS#") (class "Default")
      (node (ref "U6") (pin "53") (pinfunction "RTS#_53") (pintype "passive"))
    )
    (net (code "24") (name "/WROOM_URx") (class "Default")
      (node (ref "U6") (pin "52") (pinfunction "RXD_52") (pintype "passive"))
    )
    (net (code "25") (name "/WROOM_UTx") (class "Default")
      (node (ref "U6") (pin "48") (pinfunction "TXD_48") (pintype "passive"))
    )
    (net (code "26") (name "3V3_DEB") (class "Default")
      (node (ref "C55") (pin "1") (pinfunction "1_1") (pintype "passive"))
      (node (ref "C57") (pin "1") (pinfunction "1_1") (pintype "passive"))
      (node (ref "C58") (pin "1") (pinfunction "1_1") (pintype "passive"))
      (node (ref "C69") (pin "1") (pinfunction "1_1") (pintype "passive"))
      (node (ref "C79") (pin "1") (pinfunction "1_1") (pintype "passive"))
      (node (ref "C84") (pin "1") (pinfunction "1_1") (pintype "passive"))
      (node (ref "C90") (pin "1") (pinfunction "1_1") (pintype "passive"))
      (node (ref "L4") (pin "1") (pinfunction "1_1") (pintype "passive"))
      (node (ref "L6") (pin "1") (pinfunction "1_1") (pintype "passive"))
      (node (ref "R66") (pin "2") (pinfunction "2_2") (pintype "passive"))
      (node (ref "R67") (pin "2") (pinfunction "2_2") (pintype "passive"))
      (node (ref "R68") (pin "2") (pinfunction "2_2") (pintype "passive"))
      (node (ref "R69") (pin "2") (pinfunction "2_2") (pintype "passive"))
      (node (ref "U13") (pin "6") (pinfunction "VCC_6") (pintype "passive"))
      (node (ref "U6") (pin "20") (pinfunction "VCCIO_20") (pintype "passive"))
      (node (ref "U6") (pin "31") (pinfunction "VCCIO_31") (pintype "passive"))
      (node (ref "U6") (pin "42") (pinfunction "VCCIO_42") (pintype "passive"))
      (node (ref "U6") (pin "50") (pinfunction "VREGIN_50") (pintype "passive"))
      (node (ref "U6") (pin "56") (pinfunction "VCCIO_56") (pintype "passive"))
    )
    (net (code "27") (name "GND") (class "Default")
      (node (ref "C55") (pin "2") (pinfunction "2_2") (pintype "passive"))
      (node (ref "C57") (pin "2") (pinfunction "2_2") (pintype "passive"))
      (node (ref "C58") (pin "2") (pinfunction "2_2") (pintype "passive"))
      (node (ref "C69") (pin "2") (pinfunction "2_2") (pintype "passive"))
      (node (ref "C70") (pin "2") (pinfunction "2_2") (pintype "passive"))
      (node (ref "C71") (pin "2") (pinfunction "2_2") (pintype "passive"))
      (node (ref "C72") (pin "2") (pinfunction "2_2") (pintype "passive"))
      (node (ref "C73") (pin "1") (pinfunction "1_1") (pintype "passive"))
      (node (ref "C74") (pin "1") (pinfunction "1_1") (pintype "passive"))
      (node (ref "C75") (pin "1") (pinfunction "1_1") (pintype "passive"))
      (node (ref "C79") (pin "2") (pinfunction "2_2") (pintype "passive"))
      (node (ref "C80") (pin "2") (pinfunction "2_2") (pintype "passive"))
      (node (ref "C81") (pin "1") (pinfunction "1_1") (pintype "passive"))
      (node (ref "C82") (pin "2") (pinfunction "2_2") (pintype "passive"))
      (node (ref "C83") (pin "1") (pinfunction "1_1") (pintype "passive"))
      (node (ref "C84") (pin "2") (pinfunction "2_2") (pintype "passive"))
      (node (ref "C90") (pin "2") (pinfunction "2_2") (pintype "passive"))
      (node (ref "C91") (pin "2") (pinfunction "2_2") (pintype "passive"))
      (node (ref "R126") (pin "2") (pinfunction "2_2") (pintype "passive"))
      (node (ref "R65") (pin "2") (pinfunction "2_2") (pintype "passive"))
      (node (ref "R71") (pin "1") (pinfunction "1_1") (pintype "passive"))
      (node (ref "R74") (pin "1") (pinfunction "1_1") (pintype "passive"))
      (node (ref "U13") (pin "2") (pinfunction "VSS_2") (pintype "passive"))
      (node (ref "U6") (pin "1") (pinfunction "GND_1") (pintype "passive"))
      (node (ref "U6") (pin "10") (pinfunction "AGND_10") (pintype "passive"))
      (node (ref "U6") (pin "11") (pinfunction "GND_11") (pintype "passive"))
      (node (ref "U6") (pin "13") (pinfunction "TEST_13") (pintype "passive"))
      (node (ref "U6") (pin "15") (pinfunction "GND_15") (pintype "passive"))
      (node (ref "U6") (pin "25") (pinfunction "GND_25") (pintype "passive"))
      (node (ref "U6") (pin "35") (pinfunction "GND_35") (pintype "passive"))
      (node (ref "U6") (pin "47") (pinfunction "GND_47") (pintype "passive"))
      (node (ref "U6") (pin "5") (pinfunction "GND_5") (pintype "passive"))
      (node (ref "U6") (pin "51") (pinfunction "GND_51") (pintype "passive"))
      (node (ref "Y3") (pin "2") (pinfunction "GND_2") (pintype "passive"))
      (node (ref "Y3") (pin "4") (pinfunction "GND_4") (pintype "passive"))
    )
    (net (code "28") (name "Net-(J7-Pad1)") (class "Default")
      (node (ref "J7") (pin "1") (pintype "passive"))
      (node (ref "R79") (pin "1") (pinfunction "1_1") (pintype "passive"))
    )
    (net (code "29") (name "Net-(J7-Pad3)") (class "Default")
      (node (ref "J7") (pin "3") (pintype "passive"))
      (node (ref "R54") (pin "1") (pinfunction "1_1") (pintype "passive"))
    )
    (net (code "30") (name "Net-(J7-Pad5)") (class "Default")
      (node (ref "J7") (pin "5") (pintype "passive"))
      (node (ref "R37") (pin "1") (pinfunction "1_1") (pintype "passive"))
    )
    (net (code "31") (name "Net-(J7-Pad7)") (class "Default")
      (node (ref "J7") (pin "7") (pintype "passive"))
      (node (ref "R32") (pin "1") (pinfunction "1_1") (pintype "passive"))
    )
    (net (code "32") (name "Net-(J7-Pad9)") (class "Default")
      (node (ref "J7") (pin "9") (pintype "passive"))
      (node (ref "R31") (pin "1") (pinfunction "1_1") (pintype "passive"))
    )
    (net (code "33") (name "Net-(R31-Pad2)") (class "Default")
      (node (ref "R31") (pin "2") (pinfunction "2_2") (pintype "passive"))
      (node (ref "U6") (pin "16") (pinfunction "TXD/TCK_16") (pintype "passive"))
    )
    (net (code "34") (name "Net-(R32-Pad2)") (class "Default")
      (node (ref "R32") (pin "2") (pinfunction "2_2") (pintype "passive"))
      (node (ref "U6") (pin "17") (pinfunction "RXD/TDI_17") (pintype "passive"))
    )
    (net (code "35") (name "Net-(R37-Pad2)") (class "Default")
      (node (ref "R37") (pin "2") (pinfunction "2_2") (pintype "passive"))
      (node (ref "U6") (pin "18") (pinfunction "RTS#/TDO_18") (pintype "passive"))
    )
    (net (code "36") (name "Net-(R54-Pad2)") (class "Default")
      (node (ref "R54") (pin "2") (pinfunction "2_2") (pintype "passive"))
      (node (ref "U6") (pin "19") (pinfunction "CTS#/TMS_19") (pintype "passive"))
    )
    (net (code "37") (name "Net-(R55-Pad2)") (class "Default")
      (node (ref "R55") (pin "2") (pinfunction "2_2") (pintype "passive"))
      (node (ref "U6") (pin "26") (pinfunction "TXD/TCK_26") (pintype "passive"))
    )
    (net (code "38") (name "Net-(R56-Pad2)") (class "Default")
      (node (ref "R56") (pin "2") (pinfunction "2_2") (pintype "passive"))
      (node (ref "U6") (pin "27") (pinfunction "RXD/TDI_27") (pintype "passive"))
    )
    (net (code "39") (name "Net-(R57-Pad2)") (class "Default")
      (node (ref "R57") (pin "2") (pinfunction "2_2") (pintype "passive"))
      (node (ref "U6") (pin "28") (pinfunction "RTS#/TDO_28") (pintype "passive"))
    )
    (net (code "40") (name "Net-(R62-Pad2)") (class "Default")
      (node (ref "R62") (pin "2") (pinfunction "2_2") (pintype "passive"))
      (node (ref "U6") (pin "29") (pinfunction "CTS#/TMS_29") (pintype "passive"))
    )
    (net (code "41") (name "Net-(R71-Pad2)") (class "Default")
      (node (ref "R71") (pin "2") (pinfunction "2_2") (pintype "passive"))
      (node (ref "S2") (pin "1") (pinfunction "1_1") (pintype "passive"))
      (node (ref "S2") (pin "2") (pinfunction "2_2") (pintype "passive"))
    )
    (net (code "42") (name "Net-(R79-Pad2)") (class "Default")
      (node (ref "R79") (pin "2") (pinfunction "2_2") (pintype "passive"))
      (node (ref "U6") (pin "24") (pinfunction "RI#/TXDEN*_24") (pintype "passive"))
    )
    (net (code "43") (name "Net-(U6-REF)") (class "Default")
      (node (ref "R74") (pin "2") (pinfunction "2_2") (pintype "passive"))
      (node (ref "U6") (pin "6") (pinfunction "REF_6") (pintype "passive"))
    )
    (net (code "44") (name "Net-(U6-SUSPEND)") (class "Default")
      (node (ref "R126") (pin "1") (pinfunction "1_1") (pintype "passive"))
      (node (ref "U6") (pin "36") (pinfunction "SUSPEND_36") (pintype "passive"))
    )
    (net (code "45") (name "Net-(U6-VPHY)") (class "Default")
      (node (ref "C80") (pin "1") (pinfunction "1_1") (pintype "passive"))
      (node (ref "C81") (pin "2") (pinfunction "2_2") (pintype "passive"))
      (node (ref "L4") (pin "2") (pinfunction "2_2") (pintype "passive"))
      (node (ref "U6") (pin "4") (pinfunction "VPHY_4") (pintype "passive"))
    )
    (net (code "46") (name "Net-(U6-VPLL)") (class "Default")
      (node (ref "C82") (pin "1") (pinfunction "1_1") (pintype "passive"))
      (node (ref "C83") (pin "2") (pinfunction "2_2") (pintype "passive"))
      (node (ref "L6") (pin "2") (pinfunction "2_2") (pintype "passive"))
      (node (ref "U6") (pin "9") (pinfunction "VPLL_9") (pintype "passive"))
    )
    (net (code "47") (name "Net-(U13-DO)") (class "Default")
      (node (ref "R67") (pin "1") (pinfunction "1_1") (pintype "passive"))
      (node (ref "R72") (pin "2") (pinfunction "2_2") (pintype "passive"))
      (node (ref "U13") (pin "1") (pinfunction "DO_1") (pintype "passive"))
    )
    (net (code "48") (name "unconnected-(U6-CTS#-Pad41)") (class "Default")
      (node (ref "U6") (pin "41") (pinfunction "CTS#_41") (pintype "passive+no_connect"))
    )
    (net (code "49") (name "unconnected-(U6-CTS#-Pad54)") (class "Default")
      (node (ref "U6") (pin "54") (pinfunction "CTS#_54") (pintype "passive+no_connect"))
    )
    (net (code "50") (name "unconnected-(U6-DCD#-Pad23)") (class "Default")
      (node (ref "U6") (pin "23") (pinfunction "DCD#_23") (pintype "passive+no_connect"))
    )
    (net (code "51") (name "unconnected-(U6-DCD#-Pad33)") (class "Default")
      (node (ref "U6") (pin "33") (pinfunction "DCD#_33") (pintype "passive+no_connect"))
    )
    (net (code "52") (name "unconnected-(U6-DCD#-Pad45)") (class "Default")
      (node (ref "U6") (pin "45") (pinfunction "DCD#_45") (pintype "passive+no_connect"))
    )
    (net (code "53") (name "unconnected-(U6-DCD#-Pad58)") (class "Default")
      (node (ref "U6") (pin "58") (pinfunction "DCD#_58") (pintype "passive+no_connect"))
    )
    (net (code "54") (name "unconnected-(U6-DSR#-Pad22)") (class "Default")
      (node (ref "U6") (pin "22") (pinfunction "DSR#_22") (pintype "passive+no_connect"))
    )
    (net (code "55") (name "unconnected-(U6-DSR#-Pad32)") (class "Default")
      (node (ref "U6") (pin "32") (pinfunction "DSR#_32") (pintype "passive+no_connect"))
    )
    (net (code "56") (name "unconnected-(U6-DSR#-Pad44)") (class "Default")
      (node (ref "U6") (pin "44") (pinfunction "DSR#_44") (pintype "passive+no_connect"))
    )
    (net (code "57") (name "unconnected-(U6-DSR#-Pad57)") (class "Default")
      (node (ref "U6") (pin "57") (pinfunction "DSR#_57") (pintype "passive+no_connect"))
    )
    (net (code "58") (name "unconnected-(U6-DTR#-Pad21)") (class "Default")
      (node (ref "U6") (pin "21") (pinfunction "DTR#_21") (pintype "passive+no_connect"))
    )
    (net (code "59") (name "unconnected-(U6-DTR#-Pad30)") (class "Default")
      (node (ref "U6") (pin "30") (pinfunction "DTR#_30") (pintype "passive+no_connect"))
    )
    (net (code "60") (name "unconnected-(U6-DTR#-Pad43)") (class "Default")
      (node (ref "U6") (pin "43") (pinfunction "DTR#_43") (pintype "passive+no_connect"))
    )
    (net (code "61") (name "unconnected-(U6-RI#{slash}TXDEN*-Pad34)") (class "Default")
      (node (ref "U6") (pin "34") (pinfunction "RI#/TXDEN*_34") (pintype "passive+no_connect"))
    )
    (net (code "62") (name "unconnected-(U6-RI#{slash}TXDEN*-Pad46)") (class "Default")
      (node (ref "U6") (pin "46") (pinfunction "RI#/TXDEN*_46") (pintype "passive+no_connect"))
    )
    (net (code "63") (name "unconnected-(U6-RI#{slash}TXDEN*-Pad59)") (class "Default")
      (node (ref "U6") (pin "59") (pinfunction "RI#/TXDEN*_59") (pintype "passive+no_connect"))
    )
    (net (code "64") (name "unconnected-(U6-RTS#-Pad40)") (class "Default")
      (node (ref "U6") (pin "40") (pinfunction "RTS#_40") (pintype "passive+no_connect"))
    )
  )
)
